# BPC_PWR_CONN.net
KiCad netlist of a schematic drawn in Altium Designer
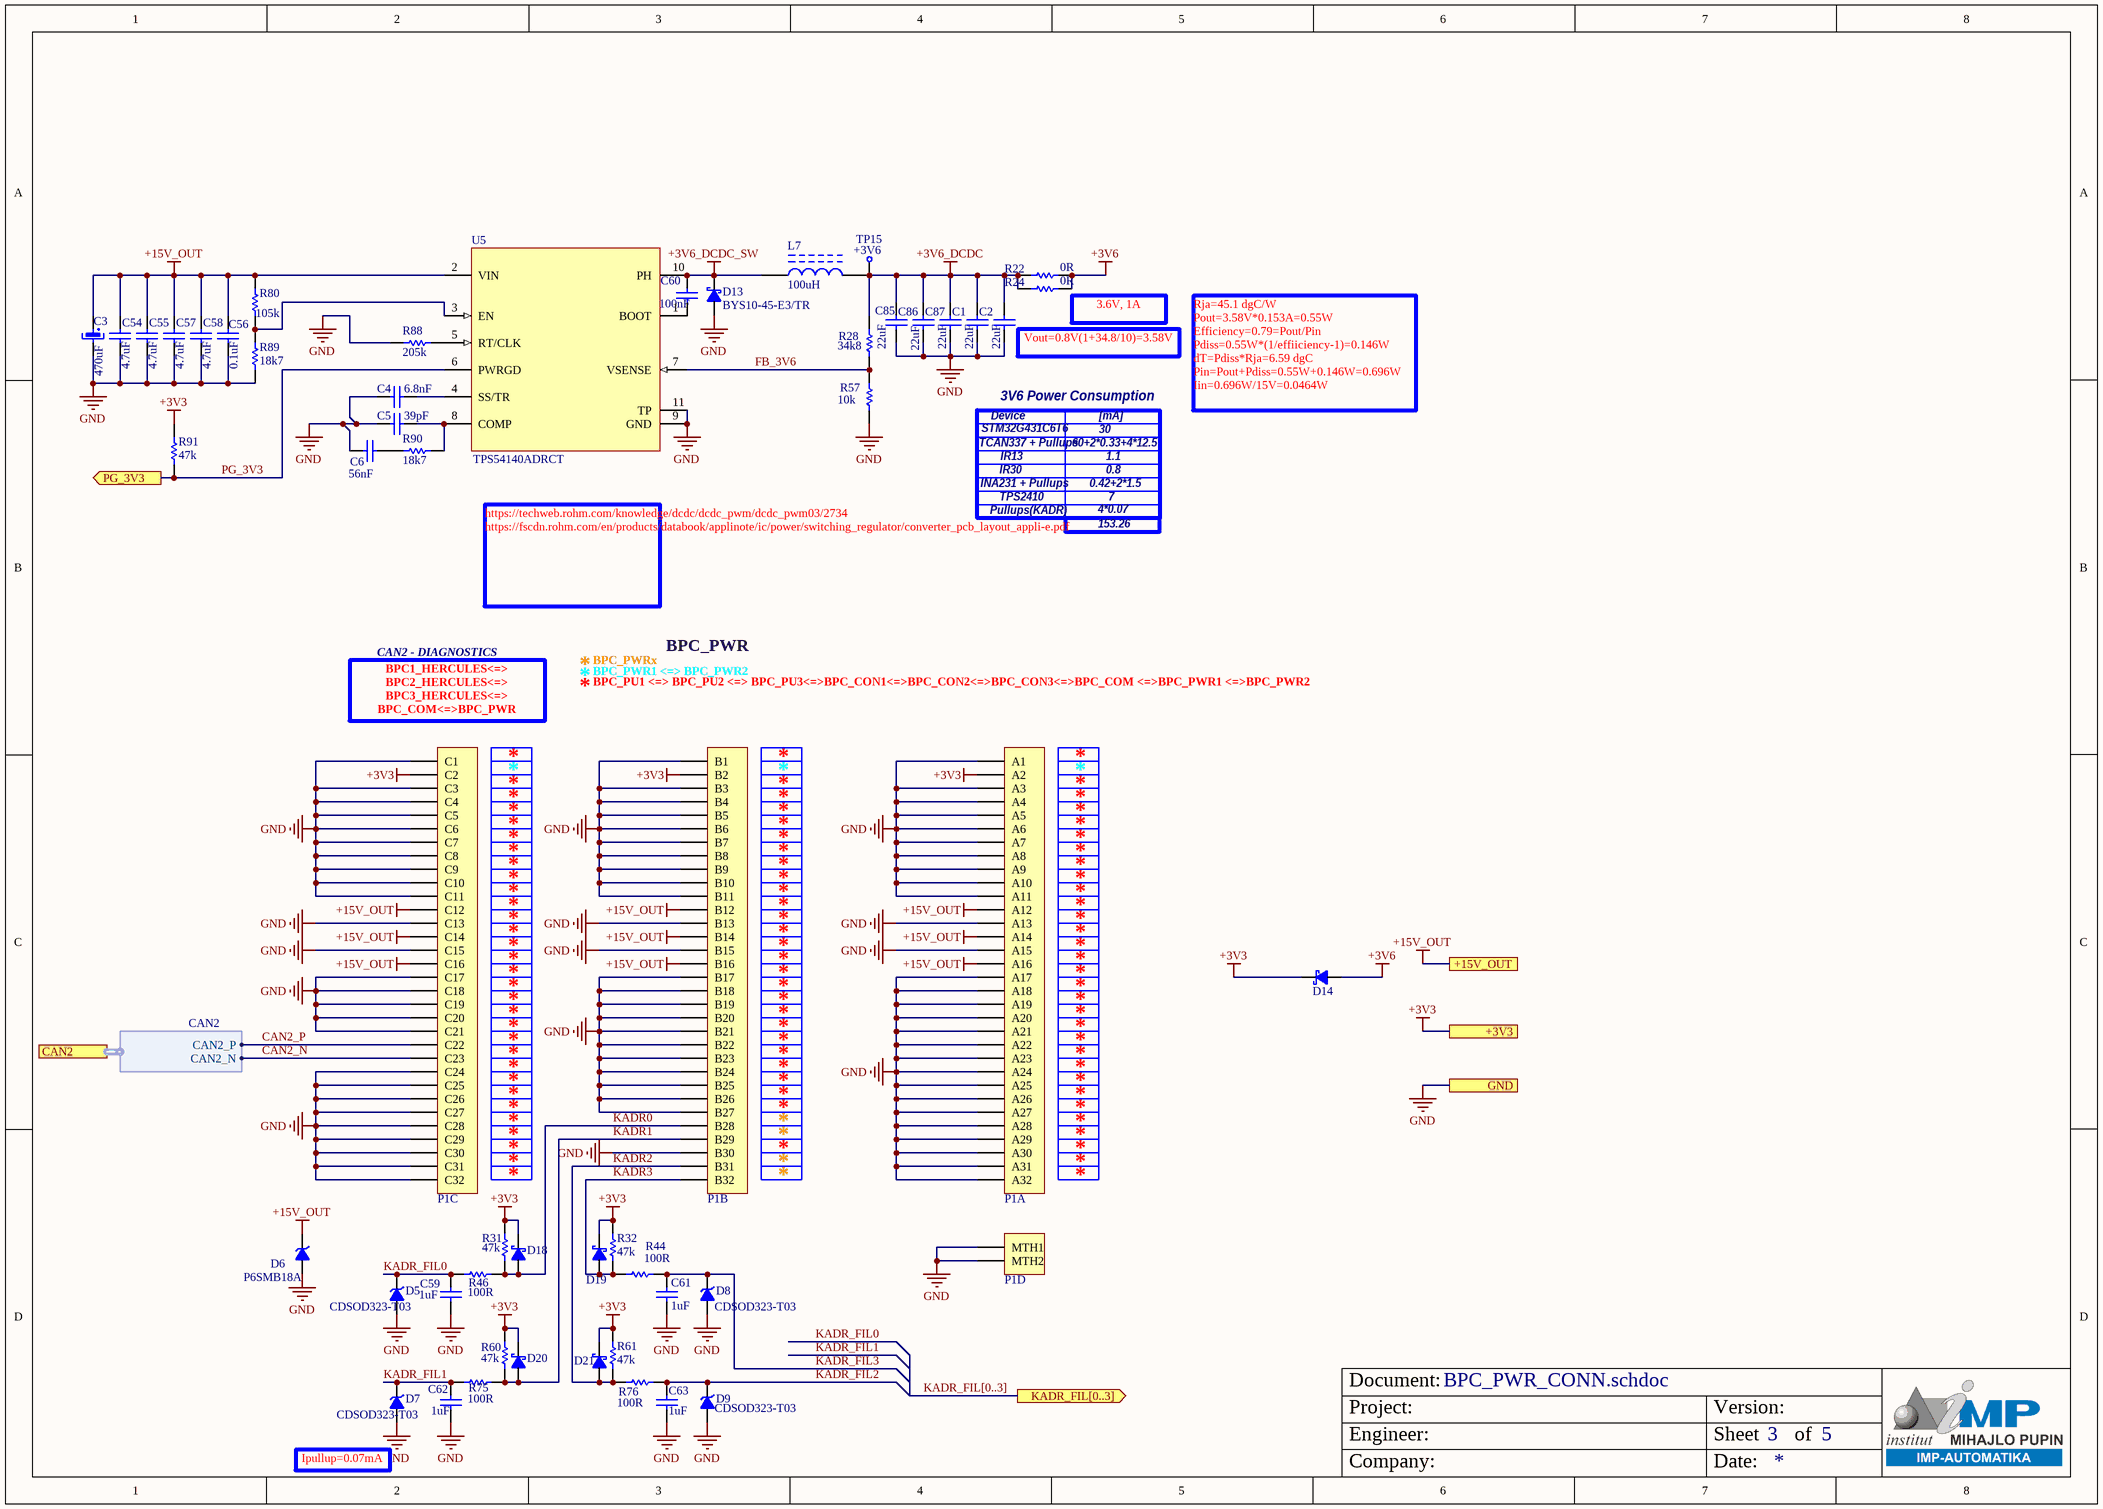
[diagram p0: BPC_PWR_CONN.schdoc]

(export (version "E")
  (design (tool "Eeschema 10.0.6"))
  (components
    (comp (ref "C1")
      (value "Ceramic Capacitor")
      (footprint "1206 C 1.80mm MS")
      (description "Ceramic Capacitor 22UF 10V X7R 1206")
      (fields
        (field (name "DISTRIBUTOR PART NUMBER") "1276-3148-1-ND")
        (field (name "MANUFACTURER") "Samsung Electro-Mechanics")
        (field (name "DB PARAMETER 1") "22uF")
      )
      (libsource (lib "MS IMP Library") (part "Cap Cer 22uF 10V X7R 1206 MS"))
    )
    (comp (ref "C2")
      (value "Ceramic Capacitor")
      (footprint "1206 C 1.80mm MS")
      (description "Ceramic Capacitor 22UF 10V X7R 1206")
      (fields
        (field (name "DISTRIBUTOR PART NUMBER") "1276-3148-1-ND")
        (field (name "MANUFACTURER") "Samsung Electro-Mechanics")
        (field (name "DB PARAMETER 1") "22uF")
      )
      (libsource (lib "MS IMP Library") (part "Cap Cer 22uF 10V X7R 1206 MS"))
    )
    (comp (ref "C3")
      (value "Electorlytic Capacitor")
      (footprint "Electrolytic Cap SMD 10x10mm Wuerth MS")
      (description "Electrolytic Capacitor 470uF 25V 10x10mm")
      (fields
        (field (name "DISTRIBUTOR PART NUMBER") "493-3944-1-ND")
        (field (name "MANUFACTURER") "Nichicon")
        (field (name "CAPACITANCE") "470uF")
      )
      (libsource (lib "MS IMP Library") (part "Cap El 470uF 25V 10x10mm Nichicon MS"))
    )
    (comp (ref "C4")
      (value "Ceramic Capacitor")
      (footprint "C0603L 0.8 MM MS")
      (description "Ceramic Capacitor 6.8nF 50V X7R 0603")
      (fields
        (field (name "DISTRIBUTOR PART NUMBER") "187-CL10B682KB8WPNC")
        (field (name "MANUFACTURER") "Samsung Electro-Mechanics")
        (field (name "CAPACITANCE") "6.8nF")
      )
      (libsource (lib "MS IMP Library") (part "Cap Cer 6.8nF 50V X7R 0603 MS"))
    )
    (comp (ref "C5")
      (value "Ceramic Capacitor")
      (footprint "C0603L 0.8 MM MS")
      (description "Ceramic Capacitor 39pF 50V C0G_NP0 0603")
      (fields
        (field (name "DISTRIBUTOR PART NUMBER") "603-CC603JRNPO9BN390")
        (field (name "MANUFACTURER") "Yageo")
        (field (name "DB PARAMETER 1") "39pF")
      )
      (libsource (lib "MS IMP Library") (part "Cap Cer 39pF 50V C0G_NP0 0603"))
    )
    (comp (ref "C6")
      (value "Ceramic Capacitor")
      (footprint "C0603L 0.8 MM MS")
      (description "Ceramic Capacitor 56nF 50V X7R 0603")
      (fields
        (field (name "DISTRIBUTOR PART NUMBER") "603-CC603KRX7R9BB563")
        (field (name "MANUFACTURER") "Yageo")
        (field (name "CAPACITANCE") "56nF")
      )
      (libsource (lib "MS IMP Library") (part "Cap Cer 56nF 50V X7R 0603 MS"))
    )
    (comp (ref "C54")
      (value "Ceramic Capacitor")
      (footprint "1210 C 1.80mm MS")
      (description "Ceramic Capacitor 4.7uF 100V X7S 1210")
      (fields
        (field (name "DISTRIBUTOR PART NUMBER") "587-5038-1-ND")
        (field (name "MANUFACTURER") "Taiyo Yuden")
        (field (name "DB PARAMETER 1") "4.7uF")
      )
      (libsource (lib "MS IMP Library") (part "Cap Cer 4.7uF 100V X7S 1210 MS"))
    )
    (comp (ref "C55")
      (value "Ceramic Capacitor")
      (footprint "1210 C 1.80mm MS")
      (description "Ceramic Capacitor 4.7uF 100V X7S 1210")
      (fields
        (field (name "DISTRIBUTOR PART NUMBER") "587-5038-1-ND")
        (field (name "MANUFACTURER") "Taiyo Yuden")
        (field (name "DB PARAMETER 1") "4.7uF")
      )
      (libsource (lib "MS IMP Library") (part "Cap Cer 4.7uF 100V X7S 1210 MS"))
    )
    (comp (ref "C56")
      (value "Ceramic Capacitor")
      (footprint "0805 C 1.27mm MS")
      (description "Ceramic Capacitor 0.1uF 100V X7R 0805")
      (fields
        (field (name "DISTRIBUTOR PART NUMBER") "810-C2012X7R2A104K")
        (field (name "MANUFACTURER") "TDK")
        (field (name "CAPACITANCE") "0.1uF")
      )
      (libsource (lib "MS IMP Library") (part "Cap Cer 0.1uF 100V X7R 0805 MS"))
    )
    (comp (ref "C57")
      (value "Ceramic Capacitor")
      (footprint "1210 C 1.80mm MS")
      (description "Ceramic Capacitor 4.7uF 100V X7S 1210")
      (fields
        (field (name "DISTRIBUTOR PART NUMBER") "587-5038-1-ND")
        (field (name "MANUFACTURER") "Taiyo Yuden")
        (field (name "DB PARAMETER 1") "4.7uF")
      )
      (libsource (lib "MS IMP Library") (part "Cap Cer 4.7uF 100V X7S 1210 MS"))
    )
    (comp (ref "C58")
      (value "Ceramic Capacitor")
      (footprint "1210 C 1.80mm MS")
      (description "Ceramic Capacitor 4.7uF 100V X7S 1210")
      (fields
        (field (name "DISTRIBUTOR PART NUMBER") "587-5038-1-ND")
        (field (name "MANUFACTURER") "Taiyo Yuden")
        (field (name "DB PARAMETER 1") "4.7uF")
      )
      (libsource (lib "MS IMP Library") (part "Cap Cer 4.7uF 100V X7S 1210 MS"))
    )
    (comp (ref "C59")
      (value "Ceramic Capacitor")
      (footprint "C0603L 0.8 MM MS")
      (description "Ceramic Capacitor 1uF 50V X5R 0603")
      (fields
        (field (name "DISTRIBUTOR PART NUMBER") "587-2400-1-ND")
        (field (name "MANUFACTURER") "Taiyo Yuden")
        (field (name "CAPACITANCE") "1uF")
      )
      (libsource (lib "MS IMP Library") (part "Cap Cer 1uF 50V X5R 0603 MS"))
    )
    (comp (ref "C60")
      (value "Ceramic Capacitor")
      (footprint "C0603L 0.8 MM MS")
      (description "Ceramic Capacitor 100nF 50V X7R 0603")
      (fields
        (field (name "DISTRIBUTOR PART NUMBER") "187-CL10B104KB8WPNC")
        (field (name "MANUFACTURER") "Samsung Electro-Mechanics")
        (field (name "CAPACITANCE") "100nF")
      )
      (libsource (lib "MS IMP Library") (part "Cap Cer 100nF 50V X7R 0603 Pt02"))
    )
    (comp (ref "C61")
      (value "Ceramic Capacitor")
      (footprint "C0603L 0.8 MM MS")
      (description "Ceramic Capacitor 1uF 50V X5R 0603")
      (fields
        (field (name "DISTRIBUTOR PART NUMBER") "587-2400-1-ND")
        (field (name "MANUFACTURER") "Taiyo Yuden")
        (field (name "CAPACITANCE") "1uF")
      )
      (libsource (lib "MS IMP Library") (part "Cap Cer 1uF 50V X5R 0603 MS"))
    )
    (comp (ref "C62")
      (value "Ceramic Capacitor")
      (footprint "C0603L 0.8 MM MS")
      (description "Ceramic Capacitor 1uF 50V X5R 0603")
      (fields
        (field (name "DISTRIBUTOR PART NUMBER") "587-2400-1-ND")
        (field (name "MANUFACTURER") "Taiyo Yuden")
        (field (name "CAPACITANCE") "1uF")
      )
      (libsource (lib "MS IMP Library") (part "Cap Cer 1uF 50V X5R 0603 MS"))
    )
    (comp (ref "C63")
      (value "Ceramic Capacitor")
      (footprint "C0603L 0.8 MM MS")
      (description "Ceramic Capacitor 1uF 50V X5R 0603")
      (fields
        (field (name "DISTRIBUTOR PART NUMBER") "587-2400-1-ND")
        (field (name "MANUFACTURER") "Taiyo Yuden")
        (field (name "CAPACITANCE") "1uF")
      )
      (libsource (lib "MS IMP Library") (part "Cap Cer 1uF 50V X5R 0603 MS"))
    )
    (comp (ref "C85")
      (value "Ceramic Capacitor")
      (footprint "1206 C 1.80mm MS")
      (description "Ceramic Capacitor 22UF 10V X7R 1206")
      (fields
        (field (name "DISTRIBUTOR PART NUMBER") "1276-3148-1-ND")
        (field (name "MANUFACTURER") "Samsung Electro-Mechanics")
        (field (name "DB PARAMETER 1") "22uF")
      )
      (libsource (lib "MS IMP Library") (part "Cap Cer 22uF 10V X7R 1206 MS"))
    )
    (comp (ref "C86")
      (value "Ceramic Capacitor")
      (footprint "1206 C 1.80mm MS")
      (description "Ceramic Capacitor 22UF 10V X7R 1206")
      (fields
        (field (name "DISTRIBUTOR PART NUMBER") "1276-3148-1-ND")
        (field (name "MANUFACTURER") "Samsung Electro-Mechanics")
        (field (name "DB PARAMETER 1") "22uF")
      )
      (libsource (lib "MS IMP Library") (part "Cap Cer 22uF 10V X7R 1206 MS"))
    )
    (comp (ref "C87")
      (value "Ceramic Capacitor")
      (footprint "1206 C 1.80mm MS")
      (description "Ceramic Capacitor 22UF 10V X7R 1206")
      (fields
        (field (name "DISTRIBUTOR PART NUMBER") "1276-3148-1-ND")
        (field (name "MANUFACTURER") "Samsung Electro-Mechanics")
        (field (name "DB PARAMETER 1") "22uF")
      )
      (libsource (lib "MS IMP Library") (part "Cap Cer 22uF 10V X7R 1206 MS"))
    )
    (comp (ref "D5")
      (value "CDSOD323-T03")
      (footprint "SOD2513X114N")
      (description "TVS Diode 3.3V 19V Udir")
      (fields
        (field (name "DISTRIBUTOR PART NUMBER") "CDSOD323-T03CT-ND")
        (field (name "MANUFACTURER") "Bourns Inc.")
      )
      (libsource (lib "MS IMP Library") (part "Dio TVS Udir 3.3V 19V CDSOD323 MS"))
    )
    (comp (ref "D6")
      (value "P6SMB18A")
      (footprint "DO-214AA SMB MS")
      (description "TVS Diode 15.3V 600W Unidirectional")
      (fields
        (field (name "DISTRIBUTOR PART NUMBER") "P6SMB18ABBCT-ND")
        (field (name "MANUFACTURER") "Bourns")
      )
      (libsource (lib "MS IMP Library") (part "Dio TVS Udir 15.3V 600W P6SMB18A MS"))
    )
    (comp (ref "D7")
      (value "CDSOD323-T03")
      (footprint "SOD2513X114N")
      (description "TVS Diode 3.3V 19V Udir")
      (fields
        (field (name "DISTRIBUTOR PART NUMBER") "CDSOD323-T03CT-ND")
        (field (name "MANUFACTURER") "Bourns Inc.")
      )
      (libsource (lib "MS IMP Library") (part "Dio TVS Udir 3.3V 19V CDSOD323 MS"))
    )
    (comp (ref "D8")
      (value "CDSOD323-T03")
      (footprint "SOD2513X114N")
      (description "TVS Diode 3.3V 19V Udir")
      (fields
        (field (name "DISTRIBUTOR PART NUMBER") "CDSOD323-T03CT-ND")
        (field (name "MANUFACTURER") "Bourns Inc.")
      )
      (libsource (lib "MS IMP Library") (part "Dio TVS Udir 3.3V 19V CDSOD323 MS"))
    )
    (comp (ref "D9")
      (value "CDSOD323-T03")
      (footprint "SOD2513X114N")
      (description "TVS Diode 3.3V 19V Udir")
      (fields
        (field (name "DISTRIBUTOR PART NUMBER") "CDSOD323-T03CT-ND")
        (field (name "MANUFACTURER") "Bourns Inc.")
      )
      (libsource (lib "MS IMP Library") (part "Dio TVS Udir 3.3V 19V CDSOD323 MS"))
    )
    (comp (ref "D13")
      (value "BYS10-45-E3/TR")
      (footprint "DO-214AC SMA MS")
      (description "Schottky Diode 1.5A 45V SMA")
      (fields
        (field (name "DISTRIBUTOR PART NUMBER") "625-BYS10-45-E3")
        (field (name "MANUFACTURER") "Vishay General Semiconductor")
      )
      (libsource (lib "MS IMP Library") (part "Dio Sch 1.5A 45V SMA MS"))
    )
    (comp (ref "D14")
      (value "PMEG3010ER,115")
      (footprint "SODFL3517X110N MS")
      (description "Schottky Diode 1A 30V SOD-123W-2")
      (fields
        (field (name "DISTRIBUTOR PART NUMBER") "771-PMEG3010ER115")
        (field (name "MANUFACTURER") "Nexperia")
      )
      (libsource (lib "MS IMP Library") (part "Dio Sch 1A 30V SOD-123W-2 MS"))
    )
    (comp (ref "D18")
      (value "PMEG3010ER,115")
      (footprint "SODFL3517X110N MS")
      (description "Schottky Diode 1A 30V SOD-123W-2")
      (fields
        (field (name "DISTRIBUTOR PART NUMBER") "771-PMEG3010ER115")
        (field (name "MANUFACTURER") "Nexperia")
      )
      (libsource (lib "MS IMP Library") (part "Dio Sch 1A 30V SOD-123W-2 MS"))
    )
    (comp (ref "D19")
      (value "PMEG3010ER,115")
      (footprint "SODFL3517X110N MS")
      (description "Schottky Diode 1A 30V SOD-123W-2")
      (fields
        (field (name "DISTRIBUTOR PART NUMBER") "771-PMEG3010ER115")
        (field (name "MANUFACTURER") "Nexperia")
      )
      (libsource (lib "MS IMP Library") (part "Dio Sch 1A 30V SOD-123W-2 MS"))
    )
    (comp (ref "D20")
      (value "PMEG3010ER,115")
      (footprint "SODFL3517X110N MS")
      (description "Schottky Diode 1A 30V SOD-123W-2")
      (fields
        (field (name "DISTRIBUTOR PART NUMBER") "771-PMEG3010ER115")
        (field (name "MANUFACTURER") "Nexperia")
      )
      (libsource (lib "MS IMP Library") (part "Dio Sch 1A 30V SOD-123W-2 MS"))
    )
    (comp (ref "D21")
      (value "PMEG3010ER,115")
      (footprint "SODFL3517X110N MS")
      (description "Schottky Diode 1A 30V SOD-123W-2")
      (fields
        (field (name "DISTRIBUTOR PART NUMBER") "771-PMEG3010ER115")
        (field (name "MANUFACTURER") "Nexperia")
      )
      (libsource (lib "MS IMP Library") (part "Dio Sch 1A 30V SOD-123W-2 MS"))
    )
    (comp (ref "L7")
      (value "Inductor")
      (footprint "INDPM120120X1020N MS")
      (description "Inductor 100uH 2.4A 0.125R")
      (fields
        (field (name "DISTRIBUTOR PART NUMBER") "994-MSS1210-104KED")
        (field (name "MANUFACTURER") "Coilcraft")
        (field (name "INDUCTANCE") "100uH")
      )
      (libsource (lib "MS IMP Library") (part "Ind 100uH 2.4A MSS1210 MS"))
    )
    (comp (ref "P1")
      (value "DIN 41612")
      (footprint "DIN 41612 96-pin Male Angled ABC MS")
      (description "Connector DIN 41612 96-pin Male C-type")
      (fields
        (field (name "DISTRIBUTOR PART NUMBER") "F5151 CM96RW")
        (field (name "MANUFACTURER") "Assmann WSW")
      )
      (libsource (lib "MS IMP Library") (part "Con DIN 41612 96-pin Male Angled ABC MS"))
    )
    (comp (ref "R22")
      (value "Resistor")
      (footprint "R0603L 0.45MM MS")
      (description "Resistor  0R 100mW 0603")
      (fields
        (field (name "DISTRIBUTOR PART NUMBER") "RMCF0603ZT0R00CT-ND")
        (field (name "MANUFACTURER") "Stackpole Electronics Inc")
        (field (name "RESISTANCE") "0R")
      )
      (libsource (lib "MS IMP Library") (part "Res 0R 100mW 0603"))
    )
    (comp (ref "R24")
      (value "Resistor")
      (footprint "R0603L 0.45MM MS")
      (description "Resistor  0R 100mW 0603")
      (fields
        (field (name "DISTRIBUTOR PART NUMBER") "RMCF0603ZT0R00CT-ND")
        (field (name "MANUFACTURER") "Stackpole Electronics Inc")
        (field (name "RESISTANCE") "0R")
      )
      (libsource (lib "MS IMP Library") (part "Res 0R 100mW 0603"))
    )
    (comp (ref "R28")
      (value "Resistor")
      (footprint "R0603L 0.45MM MS")
      (description "Resistor 34k8 1% 100mW 0603")
      (fields
        (field (name "DISTRIBUTOR PART NUMBER") "667-ERJ-3EKF3482V")
        (field (name "MANUFACTURER") "Panasonic")
        (field (name "RESISTANCE") "34k8")
      )
      (libsource (lib "MS IMP Library") (part "Res 34k8 1% 100mW 0603 MS"))
    )
    (comp (ref "R31")
      (value "Resistor")
      (footprint "R0603L 0.45MM MS")
      (description "Resistor 47k 1% 100mW 0603")
      (fields
        (field (name "DISTRIBUTOR PART NUMBER") "YAG3355CT-ND")
        (field (name "MANUFACTURER") "Yageo")
        (field (name "RESISTANCE") "47k")
      )
      (libsource (lib "MS IMP Library") (part "Res 47k 1% 100mW 0603 MS"))
    )
    (comp (ref "R32")
      (value "Resistor")
      (footprint "R0603L 0.45MM MS")
      (description "Resistor 47k 1% 100mW 0603")
      (fields
        (field (name "DISTRIBUTOR PART NUMBER") "YAG3355CT-ND")
        (field (name "MANUFACTURER") "Yageo")
        (field (name "RESISTANCE") "47k")
      )
      (libsource (lib "MS IMP Library") (part "Res 47k 1% 100mW 0603 MS"))
    )
    (comp (ref "R44")
      (value "Resistor")
      (footprint "R0603L 0.45MM MS")
      (description "Resistor 100R 1% 100mW 0603")
      (fields
        (field (name "DISTRIBUTOR PART NUMBER") "RMCF0603FT100RCT-ND")
        (field (name "MANUFACTURER") "Stackpole Electronics Inc")
        (field (name "RESISTANCE") "100R")
      )
      (libsource (lib "MS IMP Library") (part "Res 100R 1% 100mW 0603 MS Pt02"))
    )
    (comp (ref "R46")
      (value "Resistor")
      (footprint "R0603L 0.45MM MS")
      (description "Resistor 100R 1% 100mW 0603")
      (fields
        (field (name "DISTRIBUTOR PART NUMBER") "RMCF0603FT100RCT-ND")
        (field (name "MANUFACTURER") "Stackpole Electronics Inc")
        (field (name "RESISTANCE") "100R")
      )
      (libsource (lib "MS IMP Library") (part "Res 100R 1% 100mW 0603 MS Pt02"))
    )
    (comp (ref "R57")
      (value "Resistor")
      (footprint "R0603L 0.45MM MS")
      (description "Resistor 10k 1% 100mW 0603")
      (fields
        (field (name "DISTRIBUTOR PART NUMBER") "13-RC0603FR-1310KLCT-ND")
        (field (name "MANUFACTURER") "Yageo")
        (field (name "RESISTANCE") "10k")
      )
      (libsource (lib "MS IMP Library") (part "Res 10k 1% 100mW 0603"))
    )
    (comp (ref "R60")
      (value "Resistor")
      (footprint "R0603L 0.45MM MS")
      (description "Resistor 47k 1% 100mW 0603")
      (fields
        (field (name "DISTRIBUTOR PART NUMBER") "YAG3355CT-ND")
        (field (name "MANUFACTURER") "Yageo")
        (field (name "RESISTANCE") "47k")
      )
      (libsource (lib "MS IMP Library") (part "Res 47k 1% 100mW 0603 MS"))
    )
    (comp (ref "R61")
      (value "Resistor")
      (footprint "R0603L 0.45MM MS")
      (description "Resistor 47k 1% 100mW 0603")
      (fields
        (field (name "DISTRIBUTOR PART NUMBER") "YAG3355CT-ND")
        (field (name "MANUFACTURER") "Yageo")
        (field (name "RESISTANCE") "47k")
      )
      (libsource (lib "MS IMP Library") (part "Res 47k 1% 100mW 0603 MS"))
    )
    (comp (ref "R75")
      (value "Resistor")
      (footprint "R0603L 0.45MM MS")
      (description "Resistor 100R 1% 100mW 0603")
      (fields
        (field (name "DISTRIBUTOR PART NUMBER") "RMCF0603FT100RCT-ND")
        (field (name "MANUFACTURER") "Stackpole Electronics Inc")
        (field (name "RESISTANCE") "100R")
      )
      (libsource (lib "MS IMP Library") (part "Res 100R 1% 100mW 0603 MS Pt02"))
    )
    (comp (ref "R76")
      (value "Resistor")
      (footprint "R0603L 0.45MM MS")
      (description "Resistor 100R 1% 100mW 0603")
      (fields
        (field (name "DISTRIBUTOR PART NUMBER") "RMCF0603FT100RCT-ND")
        (field (name "MANUFACTURER") "Stackpole Electronics Inc")
        (field (name "RESISTANCE") "100R")
      )
      (libsource (lib "MS IMP Library") (part "Res 100R 1% 100mW 0603 MS Pt02"))
    )
    (comp (ref "R80")
      (value "Resistor")
      (footprint "R0603L 0.45MM MS")
      (description "Resistor 105k 1% 100mW 0603")
      (fields
        (field (name "DISTRIBUTOR PART NUMBER") "667-ERJ-3EKF1053V")
        (field (name "MANUFACTURER") "Panasonic")
        (field (name "RESISTANCE") "105k")
      )
      (libsource (lib "MS IMP Library") (part "Res 105k 1% 100mW 0603"))
    )
    (comp (ref "R88")
      (value "Resistor")
      (footprint "R0603L 0.45MM MS")
      (description "Resistor 205k 1% 100mW 0603")
      (fields
        (field (name "DISTRIBUTOR PART NUMBER") "667-ERJ-3EKF2053V")
        (field (name "MANUFACTURER") "Panasonic")
        (field (name "RESISTANCE") "205k")
      )
      (libsource (lib "MS IMP Library") (part "Res 205k 1% 100mW 0603 MS"))
    )
    (comp (ref "R89")
      (value "Resistor")
      (footprint "R0603L 0.45MM MS")
      (description "Resistor 18k7 1% 100mW 0603")
      (fields
        (field (name "DISTRIBUTOR PART NUMBER") "667-ERJ-3EKF1872V")
        (field (name "MANUFACTURER") "Panasonic")
        (field (name "RESISTANCE") "18k7")
      )
      (libsource (lib "MS IMP Library") (part "Res 18k7 1% 100mW 0603 MS"))
    )
    (comp (ref "R90")
      (value "Resistor")
      (footprint "R0603L 0.45MM MS")
      (description "Resistor 18k7 1% 100mW 0603")
      (fields
        (field (name "DISTRIBUTOR PART NUMBER") "667-ERJ-3EKF1872V")
        (field (name "MANUFACTURER") "Panasonic")
        (field (name "RESISTANCE") "18k7")
      )
      (libsource (lib "MS IMP Library") (part "Res 18k7 1% 100mW 0603 MS"))
    )
    (comp (ref "R91")
      (value "Resistor")
      (footprint "R0603L 0.45MM MS")
      (description "Resistor 47k 1% 100mW 0603")
      (fields
        (field (name "DISTRIBUTOR PART NUMBER") "YAG3355CT-ND")
        (field (name "MANUFACTURER") "Yageo")
        (field (name "RESISTANCE") "47k")
      )
      (libsource (lib "MS IMP Library") (part "Res 47k 1% 100mW 0603 MS"))
    )
    (comp (ref "TP15")
      (value "+3V6")
      (footprint "TP SMD 1.2mm MS")
      (description "Test Point SMD 1.2 mm No Via")
      (libsource (lib "MS IMP Library") (part "Test Point SMD"))
    )
    (comp (ref "U5")
      (value "TPS54140ADRCT")
      (footprint "DRC10_2P4X1P65_TEX MS")
      (description "IC REG BUCK ADJ 1.5A 10VSON")
      (fields
        (field (name "DISTRIBUTOR PART NUMBER") "296-30506-1-ND")
        (field (name "MANUFACTURER") "Texas Instruments")
      )
      (libsource (lib "MS IMP Library") (part "IC TPS54140ADRCT MS"))
    )
  )
  (nets
    (net (code "2") (name "+3V3") (class "Default")
      (node (ref "D14") (pin "1") (pinfunction "K_1") (pintype "passive"))
      (node (ref "D18") (pin "1") (pinfunction "K_1") (pintype "passive"))
      (node (ref "D19") (pin "1") (pinfunction "K_1") (pintype "passive"))
      (node (ref "D20") (pin "1") (pinfunction "K_1") (pintype "passive"))
      (node (ref "D21") (pin "1") (pinfunction "K_1") (pintype "passive"))
      (node (ref "P1") (pin "A2") (pinfunction "A2_A2") (pintype "passive"))
      (node (ref "P1") (pin "B2") (pinfunction "B2_B2") (pintype "passive"))
      (node (ref "P1") (pin "C2") (pinfunction "C2_C2") (pintype "passive"))
      (node (ref "R31") (pin "2") (pinfunction "2_2") (pintype "passive"))
      (node (ref "R32") (pin "2") (pinfunction "2_2") (pintype "passive"))
      (node (ref "R60") (pin "2") (pinfunction "2_2") (pintype "passive"))
      (node (ref "R61") (pin "2") (pinfunction "2_2") (pintype "passive"))
      (node (ref "R91") (pin "2") (pinfunction "2_2") (pintype "passive"))
    )
    (net (code "3") (name "+3V6") (class "Default")
      (node (ref "D14") (pin "2") (pinfunction "A_2") (pintype "passive"))
      (node (ref "R22") (pin "1") (pinfunction "1_1") (pintype "passive"))
      (node (ref "R24") (pin "1") (pinfunction "1_1") (pintype "passive"))
    )
    (net (code "4") (name "+3V6_DCDC") (class "Default")
      (node (ref "C1") (pin "1") (pinfunction "1_1") (pintype "passive"))
      (node (ref "C2") (pin "1") (pinfunction "1_1") (pintype "passive"))
      (node (ref "C85") (pin "1") (pinfunction "1_1") (pintype "passive"))
      (node (ref "C86") (pin "1") (pinfunction "1_1") (pintype "passive"))
      (node (ref "C87") (pin "1") (pinfunction "1_1") (pintype "passive"))
      (node (ref "L7") (pin "2") (pinfunction "2_2") (pintype "passive"))
      (node (ref "R22") (pin "2") (pinfunction "2_2") (pintype "passive"))
      (node (ref "R24") (pin "2") (pinfunction "2_2") (pintype "passive"))
      (node (ref "R28") (pin "2") (pinfunction "2_2") (pintype "passive"))
      (node (ref "TP15") (pin "1") (pinfunction "1_1") (pintype "passive"))
    )
    (net (code "5") (name "+3V6_DCDC_SW") (class "Default")
      (node (ref "C60") (pin "1") (pinfunction "1_1") (pintype "passive"))
      (node (ref "D13") (pin "1") (pinfunction "K_1") (pintype "passive"))
      (node (ref "L7") (pin "1") (pinfunction "1_1") (pintype "passive"))
      (node (ref "U5") (pin "10") (pinfunction "PH_10") (pintype "passive"))
    )
    (net (code "6") (name "+15V_OUT") (class "Default")
      (node (ref "C3") (pin "1") (pinfunction "1_1") (pintype "passive"))
      (node (ref "C54") (pin "1") (pinfunction "1_1") (pintype "passive"))
      (node (ref "C55") (pin "1") (pinfunction "1_1") (pintype "passive"))
      (node (ref "C56") (pin "1") (pinfunction "1_1") (pintype "passive"))
      (node (ref "C57") (pin "1") (pinfunction "1_1") (pintype "passive"))
      (node (ref "C58") (pin "1") (pinfunction "1_1") (pintype "passive"))
      (node (ref "D6") (pin "K") (pinfunction "K_K") (pintype "passive"))
      (node (ref "P1") (pin "A12") (pinfunction "A12_A12") (pintype "passive"))
      (node (ref "P1") (pin "A14") (pinfunction "A14_A14") (pintype "passive"))
      (node (ref "P1") (pin "A16") (pinfunction "A16_A16") (pintype "passive"))
      (node (ref "P1") (pin "B12") (pinfunction "B12_B12") (pintype "passive"))
      (node (ref "P1") (pin "B14") (pinfunction "B14_B14") (pintype "passive"))
      (node (ref "P1") (pin "B16") (pinfunction "B16_B16") (pintype "passive"))
      (node (ref "P1") (pin "C12") (pinfunction "C12_C12") (pintype "passive"))
      (node (ref "P1") (pin "C14") (pinfunction "C14_C14") (pintype "passive"))
      (node (ref "P1") (pin "C16") (pinfunction "C16_C16") (pintype "passive"))
      (node (ref "R80") (pin "2") (pinfunction "2_2") (pintype "passive"))
      (node (ref "U5") (pin "2") (pinfunction "VIN_2") (pintype "power_in"))
    )
    (net (code "7") (name "/CAN2_N") (class "Default")
      (node (ref "P1") (pin "C23") (pinfunction "C23_C23") (pintype "passive"))
    )
    (net (code "8") (name "/CAN2_P") (class "Default")
      (node (ref "P1") (pin "C22") (pinfunction "C22_C22") (pintype "passive"))
    )
    (net (code "9") (name "/FB_3V6") (class "Default")
      (node (ref "R28") (pin "1") (pinfunction "1_1") (pintype "passive"))
      (node (ref "R57") (pin "1") (pinfunction "1_1") (pintype "passive"))
      (node (ref "U5") (pin "7") (pinfunction "VSENSE_7") (pintype "input"))
    )
    (net (code "10") (name "/KADR0") (class "Default")
      (node (ref "D18") (pin "2") (pinfunction "A_2") (pintype "passive"))
      (node (ref "P1") (pin "B28") (pinfunction "B28_B28") (pintype "passive"))
      (node (ref "R31") (pin "1") (pinfunction "1_1") (pintype "passive"))
      (node (ref "R46") (pin "2") (pinfunction "2_2") (pintype "passive"))
    )
    (net (code "11") (name "/KADR1") (class "Default")
      (node (ref "D20") (pin "2") (pinfunction "A_2") (pintype "passive"))
      (node (ref "P1") (pin "B29") (pinfunction "B29_B29") (pintype "passive"))
      (node (ref "R60") (pin "1") (pinfunction "1_1") (pintype "passive"))
      (node (ref "R75") (pin "2") (pinfunction "2_2") (pintype "passive"))
    )
    (net (code "12") (name "/KADR2") (class "Default")
      (node (ref "D21") (pin "2") (pinfunction "A_2") (pintype "passive"))
      (node (ref "P1") (pin "B31") (pinfunction "B31_B31") (pintype "passive"))
      (node (ref "R61") (pin "1") (pinfunction "1_1") (pintype "passive"))
      (node (ref "R76") (pin "1") (pinfunction "1_1") (pintype "passive"))
    )
    (net (code "13") (name "/KADR3") (class "Default")
      (node (ref "D19") (pin "2") (pinfunction "A_2") (pintype "passive"))
      (node (ref "P1") (pin "B32") (pinfunction "B32_B32") (pintype "passive"))
      (node (ref "R32") (pin "1") (pinfunction "1_1") (pintype "passive"))
      (node (ref "R44") (pin "1") (pinfunction "1_1") (pintype "passive"))
    )
    (net (code "14") (name "/KADR_FIL0") (class "Default")
      (node (ref "C59") (pin "2") (pinfunction "2_2") (pintype "passive"))
      (node (ref "D5") (pin "K") (pinfunction "K_K") (pintype "passive"))
      (node (ref "R46") (pin "1") (pinfunction "1_1") (pintype "passive"))
    )
    (net (code "15") (name "/KADR_FIL1") (class "Default")
      (node (ref "C62") (pin "1") (pinfunction "1_1") (pintype "passive"))
      (node (ref "D7") (pin "K") (pinfunction "K_K") (pintype "passive"))
      (node (ref "R75") (pin "1") (pinfunction "1_1") (pintype "passive"))
    )
    (net (code "16") (name "/KADR_FIL2") (class "Default")
      (node (ref "C63") (pin "1") (pinfunction "1_1") (pintype "passive"))
      (node (ref "D9") (pin "K") (pinfunction "K_K") (pintype "passive"))
      (node (ref "R76") (pin "2") (pinfunction "2_2") (pintype "passive"))
    )
    (net (code "17") (name "/KADR_FIL3") (class "Default")
      (node (ref "C61") (pin "2") (pinfunction "2_2") (pintype "passive"))
      (node (ref "D8") (pin "K") (pinfunction "K_K") (pintype "passive"))
      (node (ref "R44") (pin "2") (pinfunction "2_2") (pintype "passive"))
    )
    (net (code "19") (name "/PG_3V3") (class "Default")
      (node (ref "R91") (pin "1") (pinfunction "1_1") (pintype "passive"))
      (node (ref "U5") (pin "6") (pinfunction "PWRGD_6") (pintype "open_collector"))
    )
    (net (code "21") (name "GND") (class "Default")
      (node (ref "C1") (pin "2") (pinfunction "2_2") (pintype "passive"))
      (node (ref "C2") (pin "2") (pinfunction "2_2") (pintype "passive"))
      (node (ref "C3") (pin "2") (pinfunction "2_2") (pintype "passive"))
      (node (ref "C4") (pin "1") (pinfunction "1_1") (pintype "passive"))
      (node (ref "C5") (pin "1") (pinfunction "1_1") (pintype "passive"))
      (node (ref "C54") (pin "2") (pinfunction "2_2") (pintype "passive"))
      (node (ref "C55") (pin "2") (pinfunction "2_2") (pintype "passive"))
      (node (ref "C56") (pin "2") (pinfunction "2_2") (pintype "passive"))
      (node (ref "C57") (pin "2") (pinfunction "2_2") (pintype "passive"))
      (node (ref "C58") (pin "2") (pinfunction "2_2") (pintype "passive"))
      (node (ref "C59") (pin "1") (pinfunction "1_1") (pintype "passive"))
      (node (ref "C6") (pin "1") (pinfunction "1_1") (pintype "passive"))
      (node (ref "C61") (pin "1") (pinfunction "1_1") (pintype "passive"))
      (node (ref "C62") (pin "2") (pinfunction "2_2") (pintype "passive"))
      (node (ref "C63") (pin "2") (pinfunction "2_2") (pintype "passive"))
      (node (ref "C85") (pin "2") (pinfunction "2_2") (pintype "passive"))
      (node (ref "C86") (pin "2") (pinfunction "2_2") (pintype "passive"))
      (node (ref "C87") (pin "2") (pinfunction "2_2") (pintype "passive"))
      (node (ref "D13") (pin "2") (pinfunction "A_2") (pintype "passive"))
      (node (ref "D5") (pin "A") (pinfunction "A_A") (pintype "passive"))
      (node (ref "D6") (pin "A") (pinfunction "A_A") (pintype "passive"))
      (node (ref "D7") (pin "A") (pinfunction "A_A") (pintype "passive"))
      (node (ref "D8") (pin "A") (pinfunction "A_A") (pintype "passive"))
      (node (ref "D9") (pin "A") (pinfunction "A_A") (pintype "passive"))
      (node (ref "P1") (pin "97") (pinfunction "MTH1_97") (pintype "passive"))
      (node (ref "P1") (pin "98") (pinfunction "MTH2_98") (pintype "passive"))
      (node (ref "P1") (pin "A1") (pinfunction "A1_A1") (pintype "passive"))
      (node (ref "P1") (pin "A10") (pinfunction "A10_A10") (pintype "passive"))
      (node (ref "P1") (pin "A11") (pinfunction "A11_A11") (pintype "passive"))
      (node (ref "P1") (pin "A13") (pinfunction "A13_A13") (pintype "passive"))
      (node (ref "P1") (pin "A15") (pinfunction "A15_A15") (pintype "passive"))
      (node (ref "P1") (pin "A17") (pinfunction "A17_A17") (pintype "passive"))
      (node (ref "P1") (pin "A18") (pinfunction "A18_A18") (pintype "passive"))
      (node (ref "P1") (pin "A19") (pinfunction "A19_A19") (pintype "passive"))
      (node (ref "P1") (pin "A20") (pinfunction "A20_A20") (pintype "passive"))
      (node (ref "P1") (pin "A21") (pinfunction "A21_A21") (pintype "passive"))
      (node (ref "P1") (pin "A22") (pinfunction "A22_A22") (pintype "passive"))
      (node (ref "P1") (pin "A23") (pinfunction "A23_A23") (pintype "passive"))
      (node (ref "P1") (pin "A24") (pinfunction "A24_A24") (pintype "passive"))
      (node (ref "P1") (pin "A25") (pinfunction "A25_A25") (pintype "passive"))
      (node (ref "P1") (pin "A26") (pinfunction "A26_A26") (pintype "passive"))
      (node (ref "P1") (pin "A27") (pinfunction "A27_A27") (pintype "passive"))
      (node (ref "P1") (pin "A28") (pinfunction "A28_A28") (pintype "passive"))
      (node (ref "P1") (pin "A29") (pinfunction "A29_A29") (pintype "passive"))
      (node (ref "P1") (pin "A3") (pinfunction "A3_A3") (pintype "passive"))
      (node (ref "P1") (pin "A30") (pinfunction "A30_A30") (pintype "passive"))
      (node (ref "P1") (pin "A31") (pinfunction "A31_A31") (pintype "passive"))
      (node (ref "P1") (pin "A32") (pinfunction "A32_A32") (pintype "passive"))
      (node (ref "P1") (pin "A4") (pinfunction "A4_A4") (pintype "passive"))
      (node (ref "P1") (pin "A5") (pinfunction "A5_A5") (pintype "passive"))
      (node (ref "P1") (pin "A6") (pinfunction "A6_A6") (pintype "passive"))
      (node (ref "P1") (pin "A7") (pinfunction "A7_A7") (pintype "passive"))
      (node (ref "P1") (pin "A8") (pinfunction "A8_A8") (pintype "passive"))
      (node (ref "P1") (pin "A9") (pinfunction "A9_A9") (pintype "passive"))
      (node (ref "P1") (pin "B1") (pinfunction "B1_B1") (pintype "passive"))
      (node (ref "P1") (pin "B10") (pinfunction "B10_B10") (pintype "passive"))
      (node (ref "P1") (pin "B11") (pinfunction "B11_B11") (pintype "passive"))
      (node (ref "P1") (pin "B13") (pinfunction "B13_B13") (pintype "passive"))
      (node (ref "P1") (pin "B15") (pinfunction "B15_B15") (pintype "passive"))
      (node (ref "P1") (pin "B17") (pinfunction "B17_B17") (pintype "passive"))
      (node (ref "P1") (pin "B18") (pinfunction "B18_B18") (pintype "passive"))
      (node (ref "P1") (pin "B19") (pinfunction "B19_B19") (pintype "passive"))
      (node (ref "P1") (pin "B20") (pinfunction "B20_B20") (pintype "passive"))
      (node (ref "P1") (pin "B21") (pinfunction "B21_B21") (pintype "passive"))
      (node (ref "P1") (pin "B22") (pinfunction "B22_B22") (pintype "passive"))
      (node (ref "P1") (pin "B23") (pinfunction "B23_B23") (pintype "passive"))
      (node (ref "P1") (pin "B24") (pinfunction "B24_B24") (pintype "passive"))
      (node (ref "P1") (pin "B25") (pinfunction "B25_B25") (pintype "passive"))
      (node (ref "P1") (pin "B26") (pinfunction "B26_B26") (pintype "passive"))
      (node (ref "P1") (pin "B27") (pinfunction "B27_B27") (pintype "passive"))
      (node (ref "P1") (pin "B3") (pinfunction "B3_B3") (pintype "passive"))
      (node (ref "P1") (pin "B30") (pinfunction "B30_B30") (pintype "passive"))
      (node (ref "P1") (pin "B4") (pinfunction "B4_B4") (pintype "passive"))
      (node (ref "P1") (pin "B5") (pinfunction "B5_B5") (pintype "passive"))
      (node (ref "P1") (pin "B6") (pinfunction "B6_B6") (pintype "passive"))
      (node (ref "P1") (pin "B7") (pinfunction "B7_B7") (pintype "passive"))
      (node (ref "P1") (pin "B8") (pinfunction "B8_B8") (pintype "passive"))
      (node (ref "P1") (pin "B9") (pinfunction "B9_B9") (pintype "passive"))
      (node (ref "P1") (pin "C1") (pinfunction "C1_C1") (pintype "passive"))
      (node (ref "P1") (pin "C10") (pinfunction "C10_C10") (pintype "passive"))
      (node (ref "P1") (pin "C11") (pinfunction "C11_C11") (pintype "passive"))
      (node (ref "P1") (pin "C13") (pinfunction "C13_C13") (pintype "passive"))
      (node (ref "P1") (pin "C15") (pinfunction "C15_C15") (pintype "passive"))
      (node (ref "P1") (pin "C17") (pinfunction "C17_C17") (pintype "passive"))
      (node (ref "P1") (pin "C18") (pinfunction "C18_C18") (pintype "passive"))
      (node (ref "P1") (pin "C19") (pinfunction "C19_C19") (pintype "passive"))
      (node (ref "P1") (pin "C20") (pinfunction "C20_C20") (pintype "passive"))
      (node (ref "P1") (pin "C21") (pinfunction "C21_C21") (pintype "passive"))
      (node (ref "P1") (pin "C24") (pinfunction "C24_C24") (pintype "passive"))
      (node (ref "P1") (pin "C25") (pinfunction "C25_C25") (pintype "passive"))
      (node (ref "P1") (pin "C26") (pinfunction "C26_C26") (pintype "passive"))
      (node (ref "P1") (pin "C27") (pinfunction "C27_C27") (pintype "passive"))
      (node (ref "P1") (pin "C28") (pinfunction "C28_C28") (pintype "passive"))
      (node (ref "P1") (pin "C29") (pinfunction "C29_C29") (pintype "passive"))
      (node (ref "P1") (pin "C3") (pinfunction "C3_C3") (pintype "passive"))
      (node (ref "P1") (pin "C30") (pinfunction "C30_C30") (pintype "passive"))
      (node (ref "P1") (pin "C31") (pinfunction "C31_C31") (pintype "passive"))
      (node (ref "P1") (pin "C32") (pinfunction "C32_C32") (pintype "passive"))
      (node (ref "P1") (pin "C4") (pinfunction "C4_C4") (pintype "passive"))
      (node (ref "P1") (pin "C5") (pinfunction "C5_C5") (pintype "passive"))
      (node (ref "P1") (pin "C6") (pinfunction "C6_C6") (pintype "passive"))
      (node (ref "P1") (pin "C7") (pinfunction "C7_C7") (pintype "passive"))
      (node (ref "P1") (pin "C8") (pinfunction "C8_C8") (pintype "passive"))
      (node (ref "P1") (pin "C9") (pinfunction "C9_C9") (pintype "passive"))
      (node (ref "R57") (pin "2") (pinfunction "2_2") (pintype "passive"))
      (node (ref "R88") (pin "1") (pinfunction "1_1") (pintype "passive"))
      (node (ref "R89") (pin "2") (pinfunction "2_2") (pintype "passive"))
      (node (ref "U5") (pin "11") (pinfunction "TP_11") (pintype "power_in"))
      (node (ref "U5") (pin "9") (pinfunction "GND_9") (pintype "power_in"))
    )
    (net (code "22") (name "Net-(C6-Pad2)") (class "Default")
      (node (ref "C6") (pin "2") (pinfunction "2_2") (pintype "passive"))
      (node (ref "R90") (pin "2") (pinfunction "2_2") (pintype "passive"))
    )
    (net (code "23") (name "Net-(U5-BOOT)") (class "Default")
      (node (ref "C60") (pin "2") (pinfunction "2_2") (pintype "passive"))
      (node (ref "U5") (pin "1") (pinfunction "BOOT_1") (pintype "passive"))
    )
    (net (code "24") (name "Net-(U5-COMP)") (class "Default")
      (node (ref "C5") (pin "2") (pinfunction "2_2") (pintype "passive"))
      (node (ref "R90") (pin "1") (pinfunction "1_1") (pintype "passive"))
      (node (ref "U5") (pin "8") (pinfunction "COMP_8") (pintype "passive"))
    )
    (net (code "25") (name "Net-(U5-EN)") (class "Default")
      (node (ref "R80") (pin "1") (pinfunction "1_1") (pintype "passive"))
      (node (ref "R89") (pin "1") (pinfunction "1_1") (pintype "passive"))
      (node (ref "U5") (pin "3") (pinfunction "EN_3") (pintype "input"))
    )
    (net (code "26") (name "Net-(U5-RT{slash}CLK)") (class "Default")
      (node (ref "R88") (pin "2") (pinfunction "2_2") (pintype "passive"))
      (node (ref "U5") (pin "5") (pinfunction "RT/CLK_5") (pintype "input"))
    )
    (net (code "27") (name "Net-(U5-SS{slash}TR)") (class "Default")
      (node (ref "C4") (pin "2") (pinfunction "2_2") (pintype "passive"))
      (node (ref "U5") (pin "4") (pinfunction "SS/TR_4") (pintype "passive"))
    )
  )
)
